# Fuente3_3VDC.net
KiCad netlist of a schematic drawn in Altium Designer
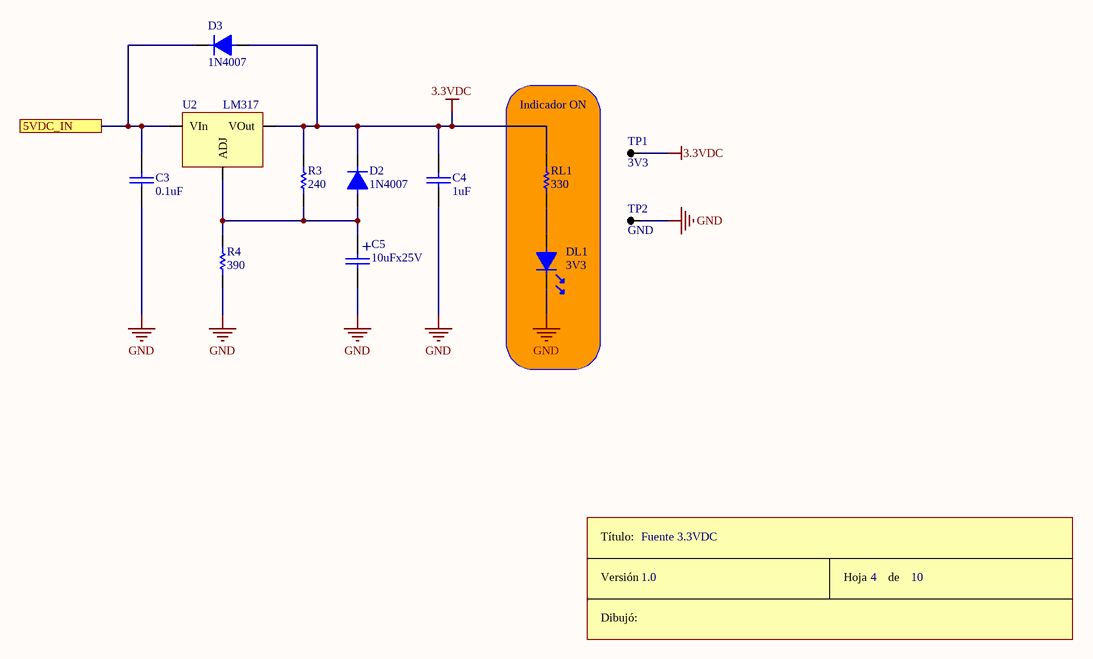
[diagram p0: Fuente3.3VDC.SchDoc]

(export (version "E")
  (design (tool "Eeschema 10.0.6"))
  (components
    (comp (ref "C3") (value "0.1uF") (footprint "CAP100") (libsource (lib "LIBEBAL") (part "CAP")))
    (comp (ref "C4") (value "1uF") (footprint "CAP200") (libsource (lib "LIBEBAL") (part "CAP")))
    (comp (ref "C5") (value "10uFx25V") (footprint "CAP100RP") (libsource (lib "LIBEBAL") (part "CAPPOL")))
    (comp (ref "D2") (value "1N4007") (footprint "DO41") (libsource (lib "LIBEBAL") (part "DIODO")))
    (comp (ref "D3") (value "1N4007") (footprint "DO41") (libsource (lib "LIBEBAL") (part "DIODO")))
    (comp (ref "DL1") (value "3V3") (footprint "LED3") (libsource (lib "LIBEBAL") (part "LED")))
    (comp (ref "R3") (value "240") (footprint "RES400") (libsource (lib "LIBEBAL") (part "RES")))
    (comp (ref "R4") (value "390") (footprint "RES400") (libsource (lib "LIBEBAL") (part "RES")))
    (comp (ref "RL1") (value "330") (footprint "RES300") (libsource (lib "LIBEBAL") (part "RES")))
    (comp (ref "ROT2") (value "Rótulo") (libsource (lib "LIB PIO IX") (part "Rótulo")))
    (comp (ref "TP1") (value "3V3") (footprint "TPTH") (libsource (lib "LIBEBAL") (part "TP")))
    (comp (ref "TP2") (value "GND") (footprint "TPTH") (libsource (lib "LIBEBAL") (part "TP")))
    (comp (ref "U2")
      (value "LM317")
      (footprint "TO-220 H")
      (description "IC REG ADJ 1.5A 3 TERM TO-220")
      (libsource (lib "LIBEBAL") (part "LM317"))
    )
  )
  (nets
    (net (code "1") (name "/5VDC_IN") (class "Default")
      (node (ref "C3") (pin "1") (pinfunction "1_1") (pintype "passive"))
      (node (ref "D3") (pin "2") (pinfunction "2_2") (pintype "passive"))
      (node (ref "U2") (pin "3") (pinfunction "VIn_3") (pintype "passive"))
    )
    (net (code "2") (name "3.3VDC") (class "Default")
      (node (ref "C4") (pin "1") (pinfunction "1_1") (pintype "passive"))
      (node (ref "D2") (pin "2") (pinfunction "2_2") (pintype "passive"))
      (node (ref "D3") (pin "1") (pinfunction "1_1") (pintype "passive"))
      (node (ref "R3") (pin "2") (pinfunction "2_2") (pintype "passive"))
      (node (ref "RL1") (pin "2") (pinfunction "2_2") (pintype "passive"))
      (node (ref "TP1") (pin "1") (pinfunction "1_1") (pintype "passive"))
      (node (ref "U2") (pin "2") (pinfunction "VOut_2") (pintype "passive"))
    )
    (net (code "3") (name "GND") (class "Default")
      (node (ref "C3") (pin "2") (pinfunction "2_2") (pintype "passive"))
      (node (ref "C4") (pin "2") (pinfunction "2_2") (pintype "passive"))
      (node (ref "C5") (pin "2") (pinfunction "2_2") (pintype "passive"))
      (node (ref "DL1") (pin "2") (pinfunction "2_2") (pintype "passive"))
      (node (ref "R4") (pin "1") (pinfunction "1_1") (pintype "passive"))
      (node (ref "TP2") (pin "1") (pinfunction "1_1") (pintype "passive"))
    )
    (net (code "4") (name "Net-(DL1-Pad1)") (class "Default")
      (node (ref "DL1") (pin "1") (pinfunction "1_1") (pintype "passive"))
      (node (ref "RL1") (pin "1") (pinfunction "1_1") (pintype "passive"))
    )
    (net (code "5") (name "Net-(U2-ADJ)") (class "Default")
      (node (ref "C5") (pin "1") (pinfunction "1_1") (pintype "passive"))
      (node (ref "D2") (pin "1") (pinfunction "1_1") (pintype "passive"))
      (node (ref "R3") (pin "1") (pinfunction "1_1") (pintype "passive"))
      (node (ref "R4") (pin "2") (pinfunction "2_2") (pintype "passive"))
      (node (ref "U2") (pin "1") (pinfunction "ADJ_1") (pintype "passive"))
    )
  )
)
